# source.net
KiCad netlist of a schematic drawn in Altium Designer
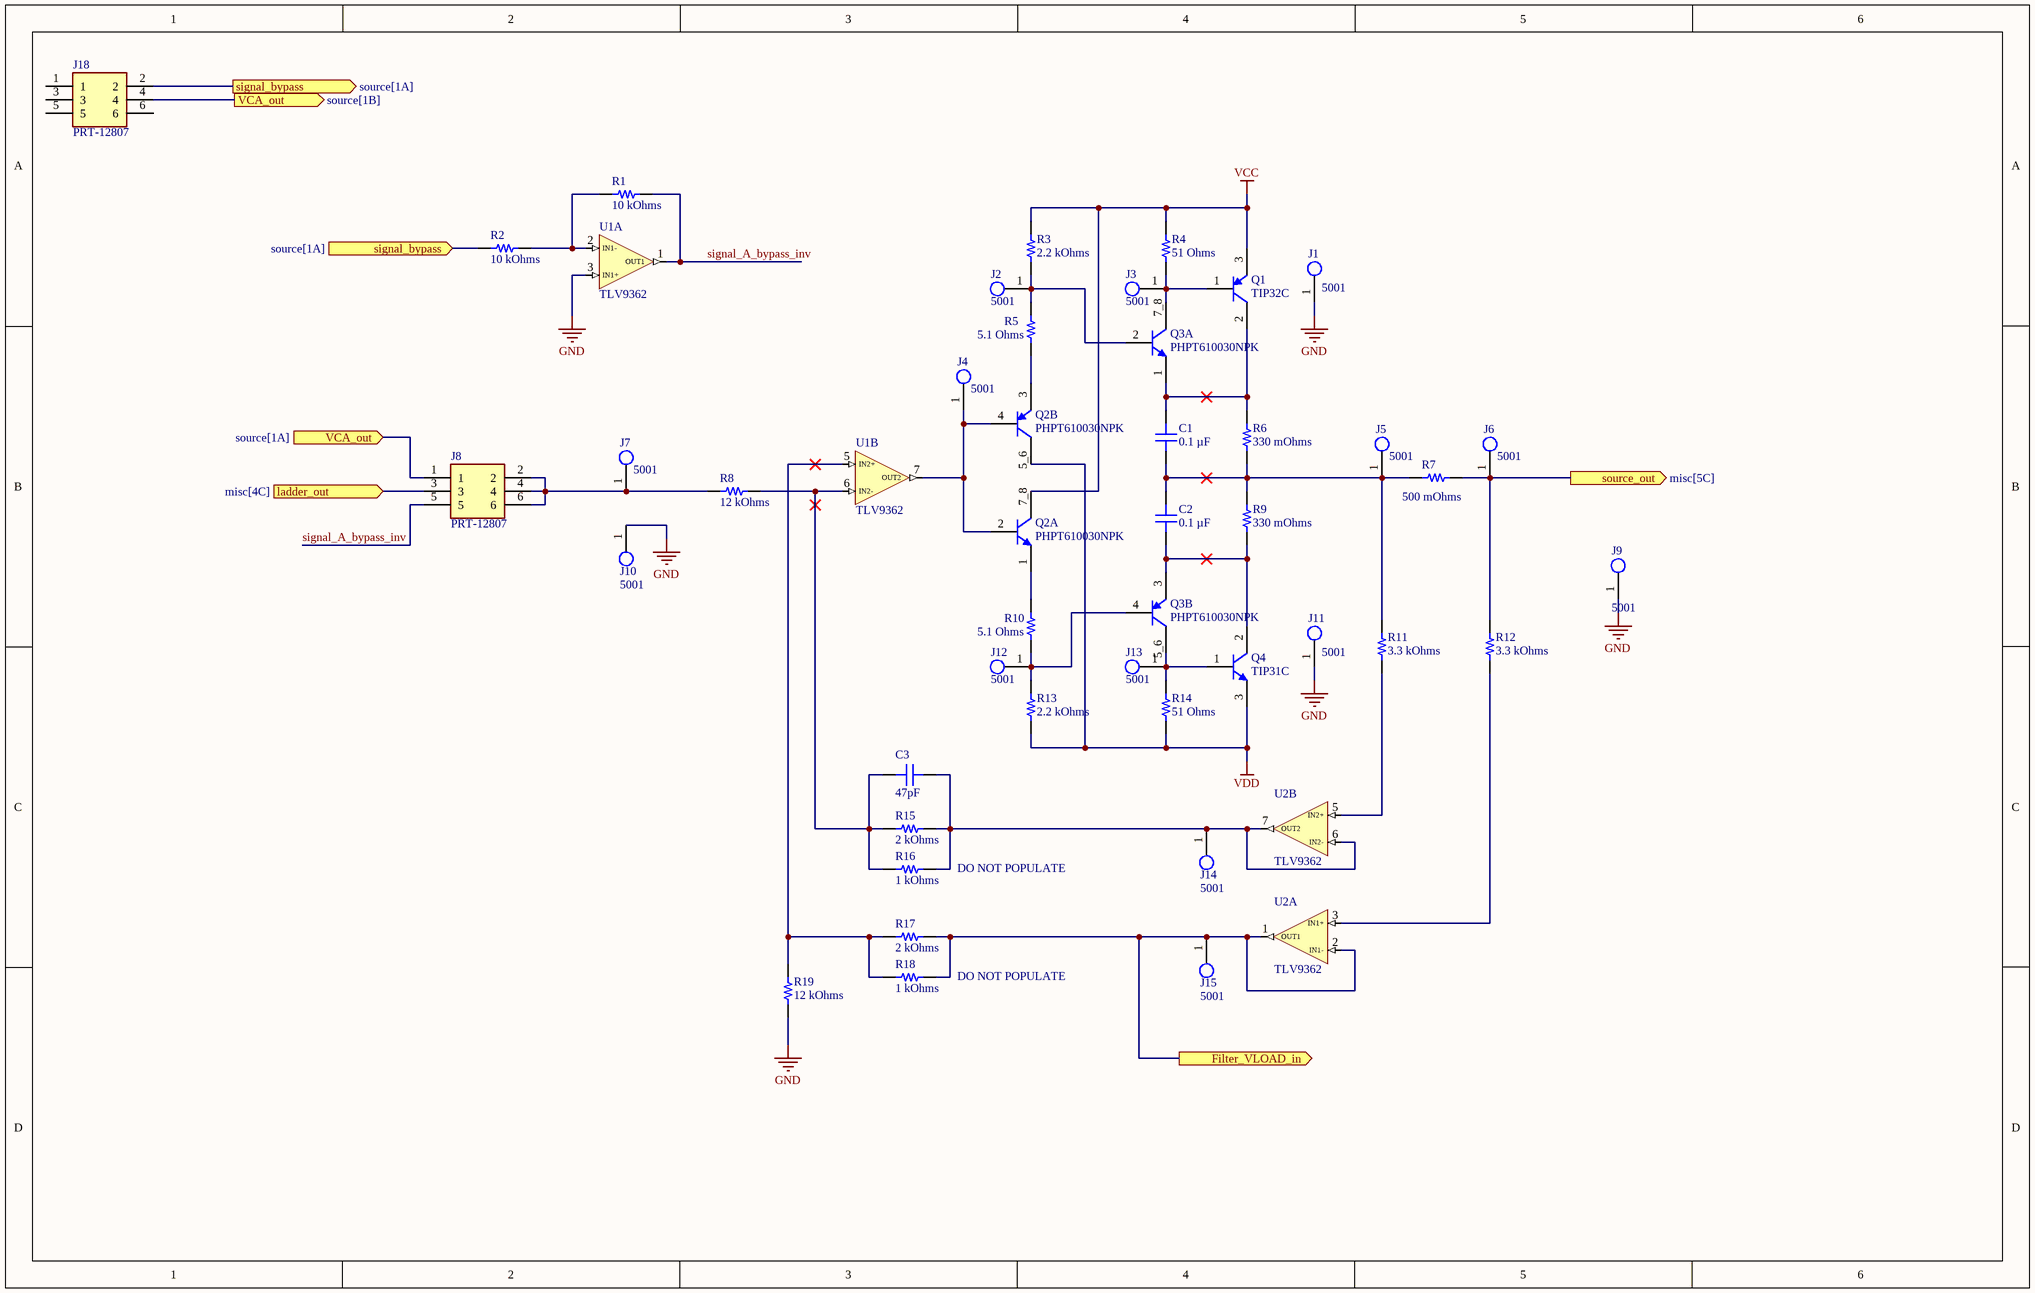
[diagram p0: source.SchDoc]

(export (version "E")
  (design (tool "Eeschema 10.0.6"))
  (components
    (comp (ref "C1")
      (value "0.1 µF")
      (footprint "CAP 1206_3216 - 0.8MM")
      (description "CAP CER 0.1UF 50V X7R 1206")
      (fields
        (field (name "PART NUMBER") "885012208087")
        (field (name "CAPACITANCE") "0.1 µF")
        (field (name "MANUFACTURER") "Würth Elektronik")
      )
      (libsource (lib "Celestial Altium Library - altium_library") (part "Capacitor"))
    )
    (comp (ref "C2")
      (value "0.1 µF")
      (footprint "CAP 1206_3216 - 0.8MM")
      (description "CAP CER 0.1UF 50V X7R 1206")
      (fields
        (field (name "PART NUMBER") "885012208087")
        (field (name "CAPACITANCE") "0.1 µF")
        (field (name "MANUFACTURER") "Würth Elektronik")
      )
      (libsource (lib "Celestial Altium Library - altium_library") (part "Capacitor"))
    )
    (comp (ref "C3")
      (value "47pF")
      (footprint "CAP 1206_3216 - 1.8MM")
      (description "CAP CER 47PF 1KV C0G/NP0 1206")
      (fields
        (field (name "PART NUMBER") "1206AA470KAT1A")
        (field (name "CAPACITANCE") "47pF")
        (field (name "MANUFACTURER") "AVX Corporation")
      )
      (libsource (lib "Celestial Altium Library - altium_library") (part "Capacitor"))
    )
    (comp (ref "J1")
      (value "5001")
      (footprint "FP-5001-MFG")
      (description "PC TEST POINT MINIATURE BLACK")
      (libsource (lib "za_koncar") (part "CMP-2000-05181-2"))
    )
    (comp (ref "J2")
      (value "5001")
      (footprint "FP-5001-MFG")
      (description "PC TEST POINT MINIATURE BLACK")
      (libsource (lib "za_koncar") (part "CMP-2000-05181-2"))
    )
    (comp (ref "J3")
      (value "5001")
      (footprint "FP-5001-MFG")
      (description "PC TEST POINT MINIATURE BLACK")
      (libsource (lib "za_koncar") (part "CMP-2000-05181-2"))
    )
    (comp (ref "J4")
      (value "5001")
      (footprint "FP-5001-MFG")
      (description "PC TEST POINT MINIATURE BLACK")
      (libsource (lib "za_koncar") (part "CMP-2000-05181-2"))
    )
    (comp (ref "J5")
      (value "5001")
      (footprint "FP-5001-MFG")
      (description "PC TEST POINT MINIATURE BLACK")
      (libsource (lib "za_koncar") (part "CMP-2000-05181-2"))
    )
    (comp (ref "J6")
      (value "5001")
      (footprint "FP-5001-MFG")
      (description "PC TEST POINT MINIATURE BLACK")
      (libsource (lib "za_koncar") (part "CMP-2000-05181-2"))
    )
    (comp (ref "J7")
      (value "5001")
      (footprint "FP-5001-MFG")
      (description "PC TEST POINT MINIATURE BLACK")
      (libsource (lib "za_koncar") (part "CMP-2000-05181-2"))
    )
    (comp (ref "J8")
      (value "PRT-12807")
      (footprint "HDRV6W82P254_2X3_762X500X884P")
      (description "Connector")
      (fields (field (name "MOUSER PART NUMBER") "474-PRT-12807"))
      (libsource (lib "za_koncar") (part "PRT-12807"))
    )
    (comp (ref "J9")
      (value "5001")
      (footprint "FP-5001-MFG")
      (description "PC TEST POINT MINIATURE BLACK")
      (libsource (lib "za_koncar") (part "CMP-2000-05181-2"))
    )
    (comp (ref "J10")
      (value "5001")
      (footprint "FP-5001-MFG")
      (description "PC TEST POINT MINIATURE BLACK")
      (libsource (lib "za_koncar") (part "CMP-2000-05181-2"))
    )
    (comp (ref "J11")
      (value "5001")
      (footprint "FP-5001-MFG")
      (description "PC TEST POINT MINIATURE BLACK")
      (libsource (lib "za_koncar") (part "CMP-2000-05181-2"))
    )
    (comp (ref "J12")
      (value "5001")
      (footprint "FP-5001-MFG")
      (description "PC TEST POINT MINIATURE BLACK")
      (libsource (lib "za_koncar") (part "CMP-2000-05181-2"))
    )
    (comp (ref "J13")
      (value "5001")
      (footprint "FP-5001-MFG")
      (description "PC TEST POINT MINIATURE BLACK")
      (libsource (lib "za_koncar") (part "CMP-2000-05181-2"))
    )
    (comp (ref "J14")
      (value "5001")
      (footprint "FP-5001-MFG")
      (description "PC TEST POINT MINIATURE BLACK")
      (libsource (lib "za_koncar") (part "CMP-2000-05181-2"))
    )
    (comp (ref "J15")
      (value "5001")
      (footprint "FP-5001-MFG")
      (description "PC TEST POINT MINIATURE BLACK")
      (libsource (lib "za_koncar") (part "CMP-2000-05181-2"))
    )
    (comp (ref "J18")
      (value "PRT-12807")
      (footprint "HDRV6W82P254_2X3_762X500X884P")
      (description "Connector")
      (fields (field (name "MOUSER PART NUMBER") "474-PRT-12807"))
      (libsource (lib "za_koncar") (part "PRT-12807"))
    )
    (comp (ref "Q1")
      (value "TIP32C")
      (footprint "ONSC-TO-220-3-221A-09")
      (description "Complementary Silicon Plastic Power Transistor, 3-Pin TO-220, Tube")
      (fields (field (name "MANUFACTURER") "On Semiconductor"))
      (libsource (lib "ON Semi General Purpose Transistors") (part "TIP32C"))
    )
    (comp (ref "Q2")
      (value "PHPT610030NPK")
      (footprint "TRANS_BUK9K18-40E,115")
      (libsource (lib "za_koncar") (part "PHPT610030NPK"))
    )
    (comp (ref "Q3")
      (value "PHPT610030NPK")
      (footprint "TRANS_BUK9K18-40E,115")
      (libsource (lib "za_koncar") (part "PHPT610030NPK"))
    )
    (comp (ref "Q4")
      (value "TIP31C")
      (footprint "ONSC-TO-220-3-221A-09")
      (description "Complementary Silicon Plastic Power Transistor, 3-Pin TO-220, Tube")
      (fields (field (name "MANUFACTURER") "On Semiconductor"))
      (libsource (lib "ON Semi General Purpose Transistors") (part "TIP31C"))
    )
    (comp (ref "R1")
      (value "10 kOhms")
      (footprint "YAGEO RES 1206_3216")
      (description "RES SMD 10K OHM 1% 1/4W 1206")
      (fields (field (name "PART NUMBER") "RT1206FRE0710KL") (field (name "MANUFACTURER") "Yageo"))
      (libsource (lib "Celestial Altium Library - altium_library") (part "Resistor"))
    )
    (comp (ref "R2")
      (value "10 kOhms")
      (footprint "YAGEO RES 1206_3216")
      (description "RES SMD 10K OHM 1% 1/4W 1206")
      (fields (field (name "PART NUMBER") "RT1206FRE0710KL") (field (name "MANUFACTURER") "Yageo"))
      (libsource (lib "Celestial Altium Library - altium_library") (part "Resistor"))
    )
    (comp (ref "R3")
      (value "2.2 kOhms")
      (footprint "RES 1206_3216")
      (description "RES SMD 2.2K OHM 5% 1/4W 1206")
      (fields
        (field (name "PART NUMBER") "ERJ-8GEYJ222V")
        (field (name "MANUFACTURER") "Panasonic Electronic Components")
      )
      (libsource (lib "Celestial Altium Library - altium_library") (part "Resistor"))
    )
    (comp (ref "R4")
      (value "51 Ohms")
      (footprint "RES 1206_3216")
      (description "RES SMD 51 OHM 5% 1/4W 1206")
      (fields
        (field (name "PART NUMBER") "ERJ-8GEYJ510V")
        (field (name "MANUFACTURER") "Panasonic Electronic Components")
      )
      (libsource (lib "Celestial Altium Library - altium_library") (part "Resistor"))
    )
    (comp (ref "R5")
      (value "5.1 Ohms")
      (footprint "RES 1206_3216")
      (description "RES SMD 5.1 OHM 5% 1/4W 1206")
      (fields
        (field (name "PART NUMBER") "ERJ-8GEYJ5R1V")
        (field (name "MANUFACTURER") "Panasonic Electronic Components")
      )
      (libsource (lib "Celestial Altium Library - altium_library") (part "Resistor"))
    )
    (comp (ref "R6")
      (value "330 mOhms")
      (footprint "STACKPOLE CSR2512")
      (description "RES 0.33 OHM 1% 2W 2512")
      (fields
        (field (name "PART NUMBER") "CSRN2512FKR330")
        (field (name "MANUFACTURER") "Stackpole Electronics Inc")
      )
      (libsource (lib "Celestial Altium Library - altium_library") (part "Resistor"))
    )
    (comp (ref "R7")
      (value "500 mOhms")
      (footprint "STACKPOLE CSR2512")
      (description "RES 0.5 OHM 1% 2W 2512")
      (fields
        (field (name "PART NUMBER") "CSRN2512FKR500")
        (field (name "MANUFACTURER") "Stackpole Electronics Inc")
      )
      (libsource (lib "Celestial Altium Library - altium_library") (part "Resistor"))
    )
    (comp (ref "R8")
      (value "12 kOhms")
      (footprint "RES 1206_3216")
      (description "RES SMD 12K OHM 0.1% 1/4W 1206")
      (fields
        (field (name "PART NUMBER") "ERA-8AEB123V")
        (field (name "MANUFACTURER") "Panasonic Electronic Components")
      )
      (libsource (lib "Celestial Altium Library - altium_library") (part "Resistor"))
    )
    (comp (ref "R9")
      (value "330 mOhms")
      (footprint "STACKPOLE CSR2512")
      (description "RES 0.33 OHM 1% 2W 2512")
      (fields
        (field (name "PART NUMBER") "CSRN2512FKR330")
        (field (name "MANUFACTURER") "Stackpole Electronics Inc")
      )
      (libsource (lib "Celestial Altium Library - altium_library") (part "Resistor"))
    )
    (comp (ref "R10")
      (value "5.1 Ohms")
      (footprint "RES 1206_3216")
      (description "RES SMD 5.1 OHM 5% 1/4W 1206")
      (fields
        (field (name "PART NUMBER") "ERJ-8GEYJ5R1V")
        (field (name "MANUFACTURER") "Panasonic Electronic Components")
      )
      (libsource (lib "Celestial Altium Library - altium_library") (part "Resistor"))
    )
    (comp (ref "R11")
      (value "3.3 kOhms")
      (footprint "YAGEO RES 1206_3216")
      (description "RES SMD 3.3K OHM 1% 1/4W 1206")
      (fields (field (name "PART NUMBER") "RT1206FRE073K3L") (field (name "MANUFACTURER") "Yageo"))
      (libsource (lib "Celestial Altium Library - altium_library") (part "Resistor"))
    )
    (comp (ref "R12")
      (value "3.3 kOhms")
      (footprint "YAGEO RES 1206_3216")
      (description "RES SMD 3.3K OHM 1% 1/4W 1206")
      (fields (field (name "PART NUMBER") "RT1206FRE073K3L") (field (name "MANUFACTURER") "Yageo"))
      (libsource (lib "Celestial Altium Library - altium_library") (part "Resistor"))
    )
    (comp (ref "R13")
      (value "2.2 kOhms")
      (footprint "RES 1206_3216")
      (description "RES SMD 2.2K OHM 5% 1/4W 1206")
      (fields
        (field (name "PART NUMBER") "ERJ-8GEYJ222V")
        (field (name "MANUFACTURER") "Panasonic Electronic Components")
      )
      (libsource (lib "Celestial Altium Library - altium_library") (part "Resistor"))
    )
    (comp (ref "R14")
      (value "51 Ohms")
      (footprint "RES 1206_3216")
      (description "RES SMD 51 OHM 5% 1/4W 1206")
      (fields
        (field (name "PART NUMBER") "ERJ-8GEYJ510V")
        (field (name "MANUFACTURER") "Panasonic Electronic Components")
      )
      (libsource (lib "Celestial Altium Library - altium_library") (part "Resistor"))
    )
    (comp (ref "R15")
      (value "2 kOhms")
      (footprint "RES 1206_3216")
      (description "RES SMD 2K OHM 0.1% 1/4W 1206")
      (fields
        (field (name "PART NUMBER") "ERA-8AEB202V")
        (field (name "MANUFACTURER") "Panasonic Electronic Components")
      )
      (libsource (lib "Celestial Altium Library - altium_library") (part "Resistor"))
    )
    (comp (ref "R16")
      (value "1 kOhms")
      (footprint "RES 1206_3216")
      (description "RES SMD 1K OHM 0.1% 1/4W 1206")
      (fields
        (field (name "PART NUMBER") "ERA-8AEB102V")
        (field (name "MANUFACTURER") "Panasonic Electronic Components")
      )
      (libsource (lib "Celestial Altium Library - altium_library") (part "Resistor"))
    )
    (comp (ref "R17")
      (value "2 kOhms")
      (footprint "RES 1206_3216")
      (description "RES SMD 2K OHM 0.1% 1/4W 1206")
      (fields
        (field (name "PART NUMBER") "ERA-8AEB202V")
        (field (name "MANUFACTURER") "Panasonic Electronic Components")
      )
      (libsource (lib "Celestial Altium Library - altium_library") (part "Resistor"))
    )
    (comp (ref "R18")
      (value "1 kOhms")
      (footprint "RES 1206_3216")
      (description "RES SMD 1K OHM 0.1% 1/4W 1206")
      (fields
        (field (name "PART NUMBER") "ERA-8AEB102V")
        (field (name "MANUFACTURER") "Panasonic Electronic Components")
      )
      (libsource (lib "Celestial Altium Library - altium_library") (part "Resistor"))
    )
    (comp (ref "R19")
      (value "12 kOhms")
      (footprint "RES 1206_3216")
      (description "RES SMD 12K OHM 0.1% 1/4W 1206")
      (fields
        (field (name "PART NUMBER") "ERA-8AEB123V")
        (field (name "MANUFACTURER") "Panasonic Electronic Components")
      )
      (libsource (lib "Celestial Altium Library - altium_library") (part "Resistor"))
    )
    (comp (ref "U1")
      (value "TLV9362")
      (footprint "SOIC8-127P600X175-8N")
      (description "TLV936x 10-MHz, 40-V, RRO, Operational Amplifie")
      (libsource (lib "za_koncar") (part "TLV9362"))
    )
    (comp (ref "U2")
      (value "TLV9362")
      (footprint "SOIC8-127P600X175-8N")
      (description "TLV936x 10-MHz, 40-V, RRO, Operational Amplifie")
      (libsource (lib "za_koncar") (part "TLV9362"))
    )
  )
  (nets
    (net (code "1") (name "/Filter_VLOAD_in") (class "Default")
      (node (ref "J15") (pin "1") (pinfunction "1_1") (pintype "passive"))
      (node (ref "R17") (pin "2") (pinfunction "2_2") (pintype "passive"))
      (node (ref "R18") (pin "2") (pinfunction "2_2") (pintype "passive"))
      (node (ref "U2") (pin "1") (pinfunction "OUT1_1") (pintype "output"))
      (node (ref "U2") (pin "2") (pinfunction "IN1-_2") (pintype "input"))
    )
    (net (code "2") (name "/VCA_out") (class "Default")
      (node (ref "J18") (pin "4") (pinfunction "4_4") (pintype "passive"))
      (node (ref "J8") (pin "1") (pinfunction "1_1") (pintype "passive"))
    )
    (net (code "3") (name "/ladder_out") (class "Default")
      (node (ref "J8") (pin "3") (pinfunction "3_3") (pintype "passive"))
    )
    (net (code "4") (name "/signal_A_bypass_inv") (class "Default")
      (node (ref "J8") (pin "5") (pinfunction "5_5") (pintype "passive"))
      (node (ref "R1") (pin "2") (pinfunction "2_2") (pintype "passive"))
      (node (ref "U1") (pin "1") (pinfunction "OUT1_1") (pintype "output"))
    )
    (net (code "5") (name "/signal_bypass") (class "Default")
      (node (ref "J18") (pin "2") (pinfunction "2_2") (pintype "passive"))
      (node (ref "R2") (pin "2") (pinfunction "2_2") (pintype "passive"))
    )
    (net (code "6") (name "/source_out") (class "Default")
      (node (ref "J6") (pin "1") (pinfunction "1_1") (pintype "passive"))
      (node (ref "R12") (pin "1") (pinfunction "1_1") (pintype "passive"))
      (node (ref "R7") (pin "1") (pinfunction "1_1") (pintype "passive"))
    )
    (net (code "7") (name "GND") (class "Default")
      (node (ref "J1") (pin "1") (pinfunction "1_1") (pintype "passive"))
      (node (ref "J10") (pin "1") (pinfunction "1_1") (pintype "passive"))
      (node (ref "J11") (pin "1") (pinfunction "1_1") (pintype "passive"))
      (node (ref "J9") (pin "1") (pinfunction "1_1") (pintype "passive"))
      (node (ref "R19") (pin "1") (pinfunction "1_1") (pintype "passive"))
      (node (ref "U1") (pin "3") (pinfunction "IN1+_3") (pintype "input"))
    )
    (net (code "8") (name "Net-(C1-Pad1)") (class "Default")
      (node (ref "C1") (pin "1") (pinfunction "1_1") (pintype "passive"))
      (node (ref "C2") (pin "2") (pinfunction "2_2") (pintype "passive"))
      (node (ref "J5") (pin "1") (pinfunction "1_1") (pintype "passive"))
      (node (ref "R11") (pin "1") (pinfunction "1_1") (pintype "passive"))
      (node (ref "R6") (pin "1") (pinfunction "1_1") (pintype "passive"))
      (node (ref "R7") (pin "2") (pinfunction "2_2") (pintype "passive"))
      (node (ref "R9") (pin "2") (pinfunction "2_2") (pintype "passive"))
    )
    (net (code "9") (name "Net-(J7-Pad1)") (class "Default")
      (node (ref "J7") (pin "1") (pinfunction "1_1") (pintype "passive"))
      (node (ref "J8") (pin "2") (pinfunction "2_2") (pintype "passive"))
      (node (ref "J8") (pin "4") (pinfunction "4_4") (pintype "passive"))
      (node (ref "J8") (pin "6") (pinfunction "6_6") (pintype "passive"))
      (node (ref "R8") (pin "2") (pinfunction "2_2") (pintype "passive"))
    )
    (net (code "10") (name "Net-(Q1-B)") (class "Default")
      (node (ref "J3") (pin "1") (pinfunction "1_1") (pintype "passive"))
      (node (ref "Q1") (pin "1") (pinfunction "B_1") (pintype "passive"))
      (node (ref "Q3") (pin "7_8") (pinfunction "C1_7_8") (pintype "passive"))
      (node (ref "R4") (pin "1") (pinfunction "1_1") (pintype "passive"))
    )
    (net (code "11") (name "Net-(Q1-C)") (class "Default")
      (node (ref "C1") (pin "2") (pinfunction "2_2") (pintype "passive"))
      (node (ref "Q1") (pin "2") (pinfunction "C_2") (pintype "passive"))
      (node (ref "Q3") (pin "1") (pinfunction "E1_1") (pintype "passive"))
      (node (ref "R6") (pin "2") (pinfunction "2_2") (pintype "passive"))
    )
    (net (code "12") (name "Net-(Q2A-B1)") (class "Default")
      (node (ref "J4") (pin "1") (pinfunction "1_1") (pintype "passive"))
      (node (ref "Q2") (pin "2") (pinfunction "B1_2") (pintype "passive"))
      (node (ref "Q2") (pin "4") (pinfunction "B2_4") (pintype "passive"))
      (node (ref "U1") (pin "7") (pinfunction "OUT2_7") (pintype "output"))
    )
    (net (code "13") (name "Net-(Q2A-E1)") (class "Default")
      (node (ref "Q2") (pin "1") (pinfunction "E1_1") (pintype "passive"))
      (node (ref "R10") (pin "2") (pinfunction "2_2") (pintype "passive"))
    )
    (net (code "14") (name "Net-(Q2B-E2)") (class "Default")
      (node (ref "Q2") (pin "3") (pinfunction "E2_3") (pintype "passive"))
      (node (ref "R5") (pin "1") (pinfunction "1_1") (pintype "passive"))
    )
    (net (code "15") (name "Net-(Q3A-B1)") (class "Default")
      (node (ref "J2") (pin "1") (pinfunction "1_1") (pintype "passive"))
      (node (ref "Q3") (pin "2") (pinfunction "B1_2") (pintype "passive"))
      (node (ref "R3") (pin "1") (pinfunction "1_1") (pintype "passive"))
      (node (ref "R5") (pin "2") (pinfunction "2_2") (pintype "passive"))
    )
    (net (code "16") (name "Net-(Q3B-B2)") (class "Default")
      (node (ref "J12") (pin "1") (pinfunction "1_1") (pintype "passive"))
      (node (ref "Q3") (pin "4") (pinfunction "B2_4") (pintype "passive"))
      (node (ref "R10") (pin "1") (pinfunction "1_1") (pintype "passive"))
      (node (ref "R13") (pin "2") (pinfunction "2_2") (pintype "passive"))
    )
    (net (code "17") (name "Net-(Q3B-C2)") (class "Default")
      (node (ref "J13") (pin "1") (pinfunction "1_1") (pintype "passive"))
      (node (ref "Q3") (pin "5_6") (pinfunction "C2_5_6") (pintype "passive"))
      (node (ref "Q4") (pin "1") (pinfunction "B_1") (pintype "passive"))
      (node (ref "R14") (pin "2") (pinfunction "2_2") (pintype "passive"))
    )
    (net (code "18") (name "Net-(Q3B-E2)") (class "Default")
      (node (ref "C2") (pin "1") (pinfunction "1_1") (pintype "passive"))
      (node (ref "Q3") (pin "3") (pinfunction "E2_3") (pintype "passive"))
      (node (ref "Q4") (pin "2") (pinfunction "C_2") (pintype "passive"))
      (node (ref "R9") (pin "1") (pinfunction "1_1") (pintype "passive"))
    )
    (net (code "19") (name "Net-(U1A-IN1-)") (class "Default")
      (node (ref "R1") (pin "1") (pinfunction "1_1") (pintype "passive"))
      (node (ref "R2") (pin "1") (pinfunction "1_1") (pintype "passive"))
      (node (ref "U1") (pin "2") (pinfunction "IN1-_2") (pintype "input"))
    )
    (net (code "20") (name "Net-(U1B-IN2+)") (class "Default")
      (node (ref "R17") (pin "1") (pinfunction "1_1") (pintype "passive"))
      (node (ref "R18") (pin "1") (pinfunction "1_1") (pintype "passive"))
      (node (ref "R19") (pin "2") (pinfunction "2_2") (pintype "passive"))
      (node (ref "U1") (pin "5") (pinfunction "IN2+_5") (pintype "input"))
    )
    (net (code "21") (name "Net-(U1B-IN2-)") (class "Default")
      (node (ref "C3") (pin "1") (pinfunction "1_1") (pintype "passive"))
      (node (ref "R15") (pin "1") (pinfunction "1_1") (pintype "passive"))
      (node (ref "R16") (pin "1") (pinfunction "1_1") (pintype "passive"))
      (node (ref "R8") (pin "1") (pinfunction "1_1") (pintype "passive"))
      (node (ref "U1") (pin "6") (pinfunction "IN2-_6") (pintype "input"))
    )
    (net (code "22") (name "Net-(U2A-IN1+)") (class "Default")
      (node (ref "R12") (pin "2") (pinfunction "2_2") (pintype "passive"))
      (node (ref "U2") (pin "3") (pinfunction "IN1+_3") (pintype "input"))
    )
    (net (code "23") (name "Net-(U2B-IN2+)") (class "Default")
      (node (ref "R11") (pin "2") (pinfunction "2_2") (pintype "passive"))
      (node (ref "U2") (pin "5") (pinfunction "IN2+_5") (pintype "input"))
    )
    (net (code "24") (name "Net-(U2B-IN2-)") (class "Default")
      (node (ref "C3") (pin "2") (pinfunction "2_2") (pintype "passive"))
      (node (ref "J14") (pin "1") (pinfunction "1_1") (pintype "passive"))
      (node (ref "R15") (pin "2") (pinfunction "2_2") (pintype "passive"))
      (node (ref "R16") (pin "2") (pinfunction "2_2") (pintype "passive"))
      (node (ref "U2") (pin "6") (pinfunction "IN2-_6") (pintype "input"))
      (node (ref "U2") (pin "7") (pinfunction "OUT2_7") (pintype "output"))
    )
    (net (code "25") (name "VCC") (class "Default")
      (node (ref "Q1") (pin "3") (pinfunction "E_3") (pintype "passive"))
      (node (ref "Q2") (pin "7_8") (pinfunction "C1_7_8") (pintype "passive"))
      (node (ref "R3") (pin "2") (pinfunction "2_2") (pintype "passive"))
      (node (ref "R4") (pin "2") (pinfunction "2_2") (pintype "passive"))
    )
    (net (code "26") (name "VDD") (class "Default")
      (node (ref "Q2") (pin "5_6") (pinfunction "C2_5_6") (pintype "passive"))
      (node (ref "Q4") (pin "3") (pinfunction "E_3") (pintype "passive"))
      (node (ref "R13") (pin "1") (pinfunction "1_1") (pintype "passive"))
      (node (ref "R14") (pin "1") (pinfunction "1_1") (pintype "passive"))
    )
    (net (code "27") (name "unconnected-(J18-Pad1)") (class "Default")
      (node (ref "J18") (pin "1") (pinfunction "1_1") (pintype "passive"))
    )
    (net (code "28") (name "unconnected-(J18-Pad3)") (class "Default")
      (node (ref "J18") (pin "3") (pinfunction "3_3") (pintype "passive"))
    )
    (net (code "29") (name "unconnected-(J18-Pad5)") (class "Default")
      (node (ref "J18") (pin "5") (pinfunction "5_5") (pintype "passive"))
    )
    (net (code "30") (name "unconnected-(J18-Pad6)") (class "Default")
      (node (ref "J18") (pin "6") (pinfunction "6_6") (pintype "passive"))
    )
  )
)
